# mega_shield_simple.net
KiCad netlist of a schematic drawn in EAGLE
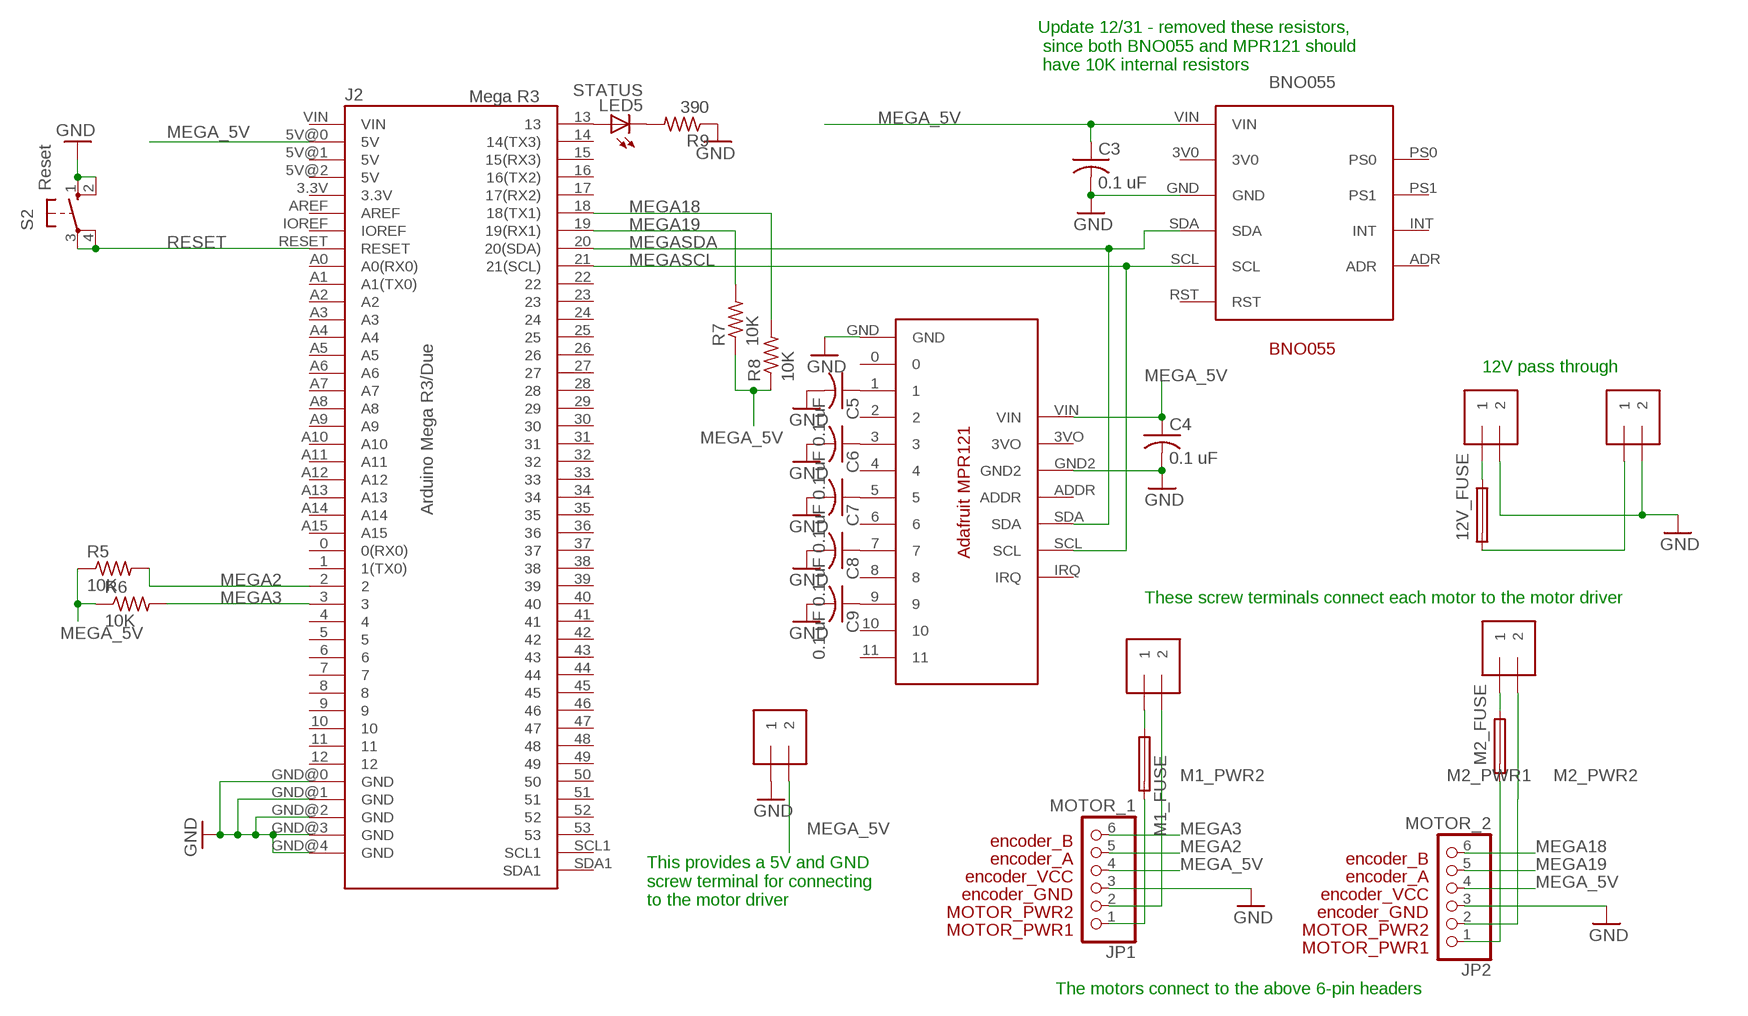
[diagram p0: schematic, sheet 1]

(export (version "E")
  (design (tool "Eeschema 10.0.6"))
  (components
    (comp (ref "5V_OUT")
      (value "1X2-3.5MM")
      (footprint "eagle-import:1X2-3.5MM")
      (libsource (lib "eagle-import") (part "1X2-3.5MM"))
    )
    (comp (ref "12V_FUSE")
      (value "3568")
      (footprint "eagle-import:3568")
      (libsource (lib "eagle-import") (part "3568"))
    )
    (comp (ref "12V_PASS1")
      (value "1X2-3.5MM")
      (footprint "eagle-import:1X2-3.5MM")
      (libsource (lib "eagle-import") (part "1X2-3.5MM"))
    )
    (comp (ref "12V_PASS2")
      (value "1X2-3.5MM")
      (footprint "eagle-import:1X2-3.5MM")
      (libsource (lib "eagle-import") (part "1X2-3.5MM"))
    )
    (comp (ref "BNO055")
      (value "BNO055")
      (footprint "eagle-import:BNO055")
      (libsource (lib "eagle-import") (part "BNO055"))
    )
    (comp (ref "C3")
      (value "0.1 uF")
      (footprint "eagle-import:C025-050X050")
      (libsource (lib "eagle-import") (part "C-US025-050X050"))
    )
    (comp (ref "C4")
      (value "0.1 uF")
      (footprint "eagle-import:C025-050X050")
      (libsource (lib "eagle-import") (part "C-US025-050X050"))
    )
    (comp (ref "C5")
      (value "0.1 uF")
      (footprint "eagle-import:C025-050X050")
      (libsource (lib "eagle-import") (part "C-US025-050X050"))
    )
    (comp (ref "C6")
      (value "0.1 uF")
      (footprint "eagle-import:C025-050X050")
      (libsource (lib "eagle-import") (part "C-US025-050X050"))
    )
    (comp (ref "C7")
      (value "0.1 uF")
      (footprint "eagle-import:C025-050X050")
      (libsource (lib "eagle-import") (part "C-US025-050X050"))
    )
    (comp (ref "C8")
      (value "0.1 uF")
      (footprint "eagle-import:C025-050X050")
      (libsource (lib "eagle-import") (part "C-US025-050X050"))
    )
    (comp (ref "C9")
      (value "0.1 uF")
      (footprint "eagle-import:C025-050X050")
      (libsource (lib "eagle-import") (part "C-US025-050X050"))
    )
    (comp (ref "J2")
      (value "Mega R3")
      (footprint "eagle-import:ARDUINO_MEGA")
      (libsource (lib "eagle-import") (part "ARDUINO-MEGAFULL"))
    )
    (comp (ref "JP1")
      (value "MOTOR_1")
      (footprint "eagle-import:1X06")
      (libsource (lib "eagle-import") (part "PINHD-1X6"))
    )
    (comp (ref "JP2")
      (value "MOTOR_2")
      (footprint "eagle-import:1X06")
      (libsource (lib "eagle-import") (part "PINHD-1X6"))
    )
    (comp (ref "LED5")
      (value "STATUS")
      (footprint "eagle-import:LED3MM")
      (libsource (lib "eagle-import") (part "LED3MM"))
    )
    (comp (ref "M1_FUSE")
      (value "FUSETE5")
      (footprint "eagle-import:TE5")
      (libsource (lib "eagle-import") (part "FUSETE5"))
    )
    (comp (ref "M1_PWR")
      (value "1X2-3.5MM")
      (footprint "eagle-import:1X2-3.5MM")
      (libsource (lib "eagle-import") (part "1X2-3.5MM"))
    )
    (comp (ref "M2_FUSE")
      (value "FUSETE5")
      (footprint "eagle-import:TE5")
      (libsource (lib "eagle-import") (part "FUSETE5"))
    )
    (comp (ref "M2_PWR")
      (value "1X2-3.5MM")
      (footprint "eagle-import:1X2-3.5MM")
      (libsource (lib "eagle-import") (part "1X2-3.5MM"))
    )
    (comp (ref "MPR121")
      (value "ADA_MPR121")
      (footprint "eagle-import:ADA_MPR121")
      (libsource (lib "eagle-import") (part "ADA_MPR121"))
    )
    (comp (ref "R5")
      (value "10K")
      (footprint "eagle-import:0207_10")
      (libsource (lib "eagle-import") (part "R-US_0207/10"))
    )
    (comp (ref "R6")
      (value "10K")
      (footprint "eagle-import:0207_10")
      (libsource (lib "eagle-import") (part "R-US_0207/10"))
    )
    (comp (ref "R7")
      (value "10K")
      (footprint "eagle-import:0207_10")
      (libsource (lib "eagle-import") (part "R-US_0207/10"))
    )
    (comp (ref "R8")
      (value "10K")
      (footprint "eagle-import:0207_10")
      (libsource (lib "eagle-import") (part "R-US_0207/10"))
    )
    (comp (ref "R9")
      (value "390")
      (footprint "eagle-import:0207_10")
      (libsource (lib "eagle-import") (part "R-US_0207/10"))
    )
    (comp (ref "S2")
      (value "Reset")
      (footprint "eagle-import:B3F-10XX")
      (fields (field (name "MPN") "B3F-1000"))
      (libsource (lib "eagle-import") (part "10-XX"))
    )
  )
  (nets
    (net (code "1") (name "/M1_PWR2") (class "Default")
      (node (ref "JP1") (pin "2") (pinfunction "2_2") (pintype "passive"))
      (node (ref "M1_PWR") (pin "2") (pinfunction "2_2") (pintype "passive"))
    )
    (net (code "2") (name "/M2_PWR1") (class "Default")
      (node (ref "JP2") (pin "1") (pinfunction "1_1") (pintype "passive"))
      (node (ref "M2_FUSE") (pin "2") (pinfunction "2_2") (pintype "passive"))
    )
    (net (code "3") (name "/M2_PWR2") (class "Default")
      (node (ref "JP2") (pin "2") (pinfunction "2_2") (pintype "passive"))
      (node (ref "M2_PWR") (pin "2") (pinfunction "2_2") (pintype "passive"))
    )
    (net (code "4") (name "/MEGA2") (class "Default")
      (node (ref "J2") (pin "2") (pinfunction "2_2") (pintype "bidirectional"))
      (node (ref "JP1") (pin "5") (pinfunction "5_5") (pintype "passive"))
      (node (ref "R5") (pin "2") (pinfunction "2_2") (pintype "passive"))
    )
    (net (code "5") (name "/MEGA3") (class "Default")
      (node (ref "J2") (pin "3") (pinfunction "3_3") (pintype "bidirectional"))
      (node (ref "JP1") (pin "6") (pinfunction "6_6") (pintype "passive"))
      (node (ref "R6") (pin "2") (pinfunction "2_2") (pintype "passive"))
    )
    (net (code "6") (name "/MEGA18") (class "Default")
      (node (ref "J2") (pin "18") (pinfunction "18(TX1)_18") (pintype "bidirectional"))
      (node (ref "JP2") (pin "6") (pinfunction "6_6") (pintype "passive"))
      (node (ref "R8") (pin "2") (pinfunction "2_2") (pintype "passive"))
    )
    (net (code "7") (name "/MEGA19") (class "Default")
      (node (ref "J2") (pin "19") (pinfunction "19(RX1)_19") (pintype "bidirectional"))
      (node (ref "JP2") (pin "5") (pinfunction "5_5") (pintype "passive"))
      (node (ref "R7") (pin "2") (pinfunction "2_2") (pintype "passive"))
    )
    (net (code "8") (name "/MEGASCL") (class "Default")
      (node (ref "BNO055") (pin "SCL") (pinfunction "SCL_SCL") (pintype "bidirectional"))
      (node (ref "J2") (pin "21") (pinfunction "21(SCL)_21") (pintype "bidirectional"))
      (node (ref "MPR121") (pin "SCL") (pinfunction "SCL_SCL") (pintype "bidirectional"))
    )
    (net (code "9") (name "/MEGASDA") (class "Default")
      (node (ref "BNO055") (pin "SDA") (pinfunction "SDA_SDA") (pintype "bidirectional"))
      (node (ref "J2") (pin "20") (pinfunction "20(SDA)_20") (pintype "bidirectional"))
      (node (ref "MPR121") (pin "SDA") (pinfunction "SDA_SDA") (pintype "bidirectional"))
    )
    (net (code "10") (name "/MEGA_5V") (class "Default")
      (node (ref "5V_OUT") (pin "2") (pinfunction "2_2") (pintype "passive"))
      (node (ref "BNO055") (pin "VIN") (pinfunction "VIN_VIN") (pintype "bidirectional"))
      (node (ref "C3") (pin "1") (pinfunction "1_1") (pintype "passive"))
      (node (ref "C4") (pin "1") (pinfunction "1_1") (pintype "passive"))
      (node (ref "J2") (pin "5V@0") (pinfunction "5V_5V@0") (pintype "bidirectional"))
      (node (ref "JP1") (pin "4") (pinfunction "4_4") (pintype "passive"))
      (node (ref "JP2") (pin "4") (pinfunction "4_4") (pintype "passive"))
      (node (ref "MPR121") (pin "VIN") (pinfunction "VIN_VIN") (pintype "bidirectional"))
      (node (ref "R5") (pin "1") (pinfunction "1_1") (pintype "passive"))
      (node (ref "R6") (pin "1") (pinfunction "1_1") (pintype "passive"))
      (node (ref "R7") (pin "1") (pinfunction "1_1") (pintype "passive"))
      (node (ref "R8") (pin "1") (pinfunction "1_1") (pintype "passive"))
    )
    (net (code "11") (name "/RESET") (class "Default")
      (node (ref "J2") (pin "RESET") (pinfunction "RESET_RESET") (pintype "bidirectional"))
      (node (ref "S2") (pin "3") (pinfunction "P_3") (pintype "passive"))
      (node (ref "S2") (pin "4") (pinfunction "P1_4") (pintype "passive"))
    )
    (net (code "12") (name "GND") (class "Default")
      (node (ref "12V_PASS1") (pin "2") (pinfunction "2_2") (pintype "passive"))
      (node (ref "12V_PASS2") (pin "2") (pinfunction "2_2") (pintype "passive"))
      (node (ref "5V_OUT") (pin "1") (pinfunction "1_1") (pintype "passive"))
      (node (ref "BNO055") (pin "GND") (pinfunction "GND_GND") (pintype "bidirectional"))
      (node (ref "C3") (pin "2") (pinfunction "2_2") (pintype "passive"))
      (node (ref "C4") (pin "2") (pinfunction "2_2") (pintype "passive"))
      (node (ref "C5") (pin "2") (pinfunction "2_2") (pintype "passive"))
      (node (ref "C6") (pin "2") (pinfunction "2_2") (pintype "passive"))
      (node (ref "C7") (pin "2") (pinfunction "2_2") (pintype "passive"))
      (node (ref "C8") (pin "2") (pinfunction "2_2") (pintype "passive"))
      (node (ref "C9") (pin "2") (pinfunction "2_2") (pintype "passive"))
      (node (ref "J2") (pin "GND@0") (pinfunction "GND_GND@0") (pintype "bidirectional"))
      (node (ref "J2") (pin "GND@1") (pinfunction "GND_GND@1") (pintype "bidirectional"))
      (node (ref "J2") (pin "GND@2") (pinfunction "GND_GND@2") (pintype "bidirectional"))
      (node (ref "J2") (pin "GND@3") (pinfunction "GND_GND@3") (pintype "bidirectional"))
      (node (ref "J2") (pin "GND@4") (pinfunction "GND_GND@4") (pintype "bidirectional"))
      (node (ref "JP1") (pin "3") (pinfunction "3_3") (pintype "passive"))
      (node (ref "JP2") (pin "3") (pinfunction "3_3") (pintype "passive"))
      (node (ref "MPR121") (pin "GND") (pinfunction "GND_GND") (pintype "bidirectional"))
      (node (ref "MPR121") (pin "GND2") (pinfunction "GND2_GND2") (pintype "bidirectional"))
      (node (ref "R9") (pin "1") (pinfunction "1_1") (pintype "passive"))
      (node (ref "S2") (pin "1") (pinfunction "S_1") (pintype "passive"))
      (node (ref "S2") (pin "2") (pinfunction "S1_2") (pintype "passive"))
    )
    (net (code "13") (name "Net-(12V_FUSE-1-Pad2)") (class "Default")
      (node (ref "12V_FUSE") (pin "1") (pinfunction "1_1") (pintype "passive"))
      (node (ref "12V_FUSE") (pin "2") (pinfunction "1_2") (pintype "passive"))
      (node (ref "12V_PASS2") (pin "1") (pinfunction "1_1") (pintype "passive"))
    )
    (net (code "14") (name "Net-(12V_FUSE-2-Pad3)") (class "Default")
      (node (ref "12V_FUSE") (pin "3") (pinfunction "2_3") (pintype "passive"))
      (node (ref "12V_FUSE") (pin "4") (pinfunction "2_4") (pintype "passive"))
      (node (ref "12V_PASS1") (pin "1") (pinfunction "1_1") (pintype "passive"))
    )
    (net (code "15") (name "Net-(C5-Pad1)") (class "Default")
      (node (ref "C5") (pin "1") (pinfunction "1_1") (pintype "passive"))
      (node (ref "MPR121") (pin "1") (pinfunction "1_1") (pintype "bidirectional"))
    )
    (net (code "16") (name "Net-(C6-Pad1)") (class "Default")
      (node (ref "C6") (pin "1") (pinfunction "1_1") (pintype "passive"))
      (node (ref "MPR121") (pin "3") (pinfunction "3_3") (pintype "bidirectional"))
    )
    (net (code "17") (name "Net-(C7-Pad1)") (class "Default")
      (node (ref "C7") (pin "1") (pinfunction "1_1") (pintype "passive"))
      (node (ref "MPR121") (pin "5") (pinfunction "5_5") (pintype "bidirectional"))
    )
    (net (code "18") (name "Net-(C8-Pad1)") (class "Default")
      (node (ref "C8") (pin "1") (pinfunction "1_1") (pintype "passive"))
      (node (ref "MPR121") (pin "7") (pinfunction "7_7") (pintype "bidirectional"))
    )
    (net (code "19") (name "Net-(C9-Pad1)") (class "Default")
      (node (ref "C9") (pin "1") (pinfunction "1_1") (pintype "passive"))
      (node (ref "MPR121") (pin "9") (pinfunction "9_9") (pintype "bidirectional"))
    )
    (net (code "20") (name "Net-(J2-Pad13)") (class "Default")
      (node (ref "J2") (pin "13") (pinfunction "13_13") (pintype "bidirectional"))
      (node (ref "LED5") (pin "A") (pinfunction "A_A") (pintype "passive"))
    )
    (net (code "21") (name "Net-(JP1-Pad1)") (class "Default")
      (node (ref "JP1") (pin "1") (pinfunction "1_1") (pintype "passive"))
      (node (ref "M1_FUSE") (pin "2") (pinfunction "2_2") (pintype "passive"))
    )
    (net (code "22") (name "Net-(LED5-C)") (class "Default")
      (node (ref "LED5") (pin "K") (pinfunction "C_K") (pintype "passive"))
      (node (ref "R9") (pin "2") (pinfunction "2_2") (pintype "passive"))
    )
    (net (code "23") (name "Net-(M1_FUSE-Pad1)") (class "Default")
      (node (ref "M1_FUSE") (pin "1") (pinfunction "1_1") (pintype "passive"))
      (node (ref "M1_PWR") (pin "1") (pinfunction "1_1") (pintype "passive"))
    )
    (net (code "24") (name "Net-(M2_FUSE-Pad1)") (class "Default")
      (node (ref "M2_FUSE") (pin "1") (pinfunction "1_1") (pintype "passive"))
      (node (ref "M2_PWR") (pin "1") (pinfunction "1_1") (pintype "passive"))
    )
    (net (code "25") (name "unconnected-(BNO055-Pad3V0)") (class "Default")
      (node (ref "BNO055") (pin "3V0") (pinfunction "3V0_3V0") (pintype "bidirectional"))
    )
    (net (code "26") (name "unconnected-(BNO055-PadADR)") (class "Default")
      (node (ref "BNO055") (pin "ADR") (pinfunction "ADR_ADR") (pintype "bidirectional"))
    )
    (net (code "27") (name "unconnected-(BNO055-PadINT)") (class "Default")
      (node (ref "BNO055") (pin "INT") (pinfunction "INT_INT") (pintype "bidirectional"))
    )
    (net (code "28") (name "unconnected-(BNO055-PadPS0)") (class "Default")
      (node (ref "BNO055") (pin "PS0") (pinfunction "PS0_PS0") (pintype "bidirectional"))
    )
    (net (code "29") (name "unconnected-(BNO055-PadPS1)") (class "Default")
      (node (ref "BNO055") (pin "PS1") (pinfunction "PS1_PS1") (pintype "bidirectional"))
    )
    (net (code "30") (name "unconnected-(BNO055-PadRST)") (class "Default")
      (node (ref "BNO055") (pin "RST") (pinfunction "RST_RST") (pintype "bidirectional"))
    )
    (net (code "31") (name "unconnected-(J2-0(RX0)-Pad0)") (class "Default")
      (node (ref "J2") (pin "0") (pinfunction "0(RX0)_0") (pintype "bidirectional"))
    )
    (net (code "32") (name "unconnected-(J2-1(TX0)-Pad1)") (class "Default")
      (node (ref "J2") (pin "1") (pinfunction "1(TX0)_1") (pintype "bidirectional"))
    )
    (net (code "33") (name "unconnected-(J2-5V-Pad5V@1)") (class "Default")
      (node (ref "J2") (pin "5V@1") (pinfunction "5V_5V@1") (pintype "bidirectional"))
    )
    (net (code "34") (name "unconnected-(J2-5V-Pad5V@2)") (class "Default")
      (node (ref "J2") (pin "5V@2") (pinfunction "5V_5V@2") (pintype "bidirectional"))
    )
    (net (code "35") (name "unconnected-(J2-14(TX3)-Pad14)") (class "Default")
      (node (ref "J2") (pin "14") (pinfunction "14(TX3)_14") (pintype "bidirectional"))
    )
    (net (code "36") (name "unconnected-(J2-15(RX3)-Pad15)") (class "Default")
      (node (ref "J2") (pin "15") (pinfunction "15(RX3)_15") (pintype "bidirectional"))
    )
    (net (code "37") (name "unconnected-(J2-16(TX2)-Pad16)") (class "Default")
      (node (ref "J2") (pin "16") (pinfunction "16(TX2)_16") (pintype "bidirectional"))
    )
    (net (code "38") (name "unconnected-(J2-17(RX2)-Pad17)") (class "Default")
      (node (ref "J2") (pin "17") (pinfunction "17(RX2)_17") (pintype "bidirectional"))
    )
    (net (code "39") (name "unconnected-(J2-A0(RX0)-PadA0)") (class "Default")
      (node (ref "J2") (pin "A0") (pinfunction "A0(RX0)_A0") (pintype "bidirectional"))
    )
    (net (code "40") (name "unconnected-(J2-A1(TX0)-PadA1)") (class "Default")
      (node (ref "J2") (pin "A1") (pinfunction "A1(TX0)_A1") (pintype "bidirectional"))
    )
    (net (code "41") (name "unconnected-(J2-Pad3.3V)") (class "Default")
      (node (ref "J2") (pin "3.3V") (pinfunction "3.3V_3.3V") (pintype "bidirectional"))
    )
    (net (code "42") (name "unconnected-(J2-Pad4)") (class "Default")
      (node (ref "J2") (pin "4") (pinfunction "4_4") (pintype "bidirectional"))
    )
    (net (code "43") (name "unconnected-(J2-Pad5)") (class "Default")
      (node (ref "J2") (pin "5") (pinfunction "5_5") (pintype "bidirectional"))
    )
    (net (code "44") (name "unconnected-(J2-Pad6)") (class "Default")
      (node (ref "J2") (pin "6") (pinfunction "6_6") (pintype "bidirectional"))
    )
    (net (code "45") (name "unconnected-(J2-Pad7)") (class "Default")
      (node (ref "J2") (pin "7") (pinfunction "7_7") (pintype "bidirectional"))
    )
    (net (code "46") (name "unconnected-(J2-Pad8)") (class "Default")
      (node (ref "J2") (pin "8") (pinfunction "8_8") (pintype "bidirectional"))
    )
    (net (code "47") (name "unconnected-(J2-Pad9)") (class "Default")
      (node (ref "J2") (pin "9") (pinfunction "9_9") (pintype "bidirectional"))
    )
    (net (code "48") (name "unconnected-(J2-Pad10)") (class "Default")
      (node (ref "J2") (pin "10") (pinfunction "10_10") (pintype "bidirectional"))
    )
    (net (code "49") (name "unconnected-(J2-Pad11)") (class "Default")
      (node (ref "J2") (pin "11") (pinfunction "11_11") (pintype "bidirectional"))
    )
    (net (code "50") (name "unconnected-(J2-Pad12)") (class "Default")
      (node (ref "J2") (pin "12") (pinfunction "12_12") (pintype "bidirectional"))
    )
    (net (code "51") (name "unconnected-(J2-Pad22)") (class "Default")
      (node (ref "J2") (pin "22") (pinfunction "22_22") (pintype "bidirectional"))
    )
    (net (code "52") (name "unconnected-(J2-Pad23)") (class "Default")
      (node (ref "J2") (pin "23") (pinfunction "23_23") (pintype "bidirectional"))
    )
    (net (code "53") (name "unconnected-(J2-Pad24)") (class "Default")
      (node (ref "J2") (pin "24") (pinfunction "24_24") (pintype "bidirectional"))
    )
    (net (code "54") (name "unconnected-(J2-Pad25)") (class "Default")
      (node (ref "J2") (pin "25") (pinfunction "25_25") (pintype "bidirectional"))
    )
    (net (code "55") (name "unconnected-(J2-Pad26)") (class "Default")
      (node (ref "J2") (pin "26") (pinfunction "26_26") (pintype "bidirectional"))
    )
    (net (code "56") (name "unconnected-(J2-Pad27)") (class "Default")
      (node (ref "J2") (pin "27") (pinfunction "27_27") (pintype "bidirectional"))
    )
    (net (code "57") (name "unconnected-(J2-Pad28)") (class "Default")
      (node (ref "J2") (pin "28") (pinfunction "28_28") (pintype "bidirectional"))
    )
    (net (code "58") (name "unconnected-(J2-Pad29)") (class "Default")
      (node (ref "J2") (pin "29") (pinfunction "29_29") (pintype "bidirectional"))
    )
    (net (code "59") (name "unconnected-(J2-Pad30)") (class "Default")
      (node (ref "J2") (pin "30") (pinfunction "30_30") (pintype "bidirectional"))
    )
    (net (code "60") (name "unconnected-(J2-Pad31)") (class "Default")
      (node (ref "J2") (pin "31") (pinfunction "31_31") (pintype "bidirectional"))
    )
    (net (code "61") (name "unconnected-(J2-Pad32)") (class "Default")
      (node (ref "J2") (pin "32") (pinfunction "32_32") (pintype "bidirectional"))
    )
    (net (code "62") (name "unconnected-(J2-Pad33)") (class "Default")
      (node (ref "J2") (pin "33") (pinfunction "33_33") (pintype "bidirectional"))
    )
    (net (code "63") (name "unconnected-(J2-Pad34)") (class "Default")
      (node (ref "J2") (pin "34") (pinfunction "34_34") (pintype "bidirectional"))
    )
    (net (code "64") (name "unconnected-(J2-Pad35)") (class "Default")
      (node (ref "J2") (pin "35") (pinfunction "35_35") (pintype "bidirectional"))
    )
    (net (code "65") (name "unconnected-(J2-Pad36)") (class "Default")
      (node (ref "J2") (pin "36") (pinfunction "36_36") (pintype "bidirectional"))
    )
    (net (code "66") (name "unconnected-(J2-Pad37)") (class "Default")
      (node (ref "J2") (pin "37") (pinfunction "37_37") (pintype "bidirectional"))
    )
    (net (code "67") (name "unconnected-(J2-Pad38)") (class "Default")
      (node (ref "J2") (pin "38") (pinfunction "38_38") (pintype "bidirectional"))
    )
    (net (code "68") (name "unconnected-(J2-Pad39)") (class "Default")
      (node (ref "J2") (pin "39") (pinfunction "39_39") (pintype "bidirectional"))
    )
    (net (code "69") (name "unconnected-(J2-Pad40)") (class "Default")
      (node (ref "J2") (pin "40") (pinfunction "40_40") (pintype "bidirectional"))
    )
    (net (code "70") (name "unconnected-(J2-Pad41)") (class "Default")
      (node (ref "J2") (pin "41") (pinfunction "41_41") (pintype "bidirectional"))
    )
    (net (code "71") (name "unconnected-(J2-Pad42)") (class "Default")
      (node (ref "J2") (pin "42") (pinfunction "42_42") (pintype "bidirectional"))
    )
    (net (code "72") (name "unconnected-(J2-Pad43)") (class "Default")
      (node (ref "J2") (pin "43") (pinfunction "43_43") (pintype "bidirectional"))
    )
    (net (code "73") (name "unconnected-(J2-Pad44)") (class "Default")
      (node (ref "J2") (pin "44") (pinfunction "44_44") (pintype "bidirectional"))
    )
    (net (code "74") (name "unconnected-(J2-Pad45)") (class "Default")
      (node (ref "J2") (pin "45") (pinfunction "45_45") (pintype "bidirectional"))
    )
    (net (code "75") (name "unconnected-(J2-Pad46)") (class "Default")
      (node (ref "J2") (pin "46") (pinfunction "46_46") (pintype "bidirectional"))
    )
    (net (code "76") (name "unconnected-(J2-Pad47)") (class "Default")
      (node (ref "J2") (pin "47") (pinfunction "47_47") (pintype "bidirectional"))
    )
    (net (code "77") (name "unconnected-(J2-Pad48)") (class "Default")
      (node (ref "J2") (pin "48") (pinfunction "48_48") (pintype "bidirectional"))
    )
    (net (code "78") (name "unconnected-(J2-Pad49)") (class "Default")
      (node (ref "J2") (pin "49") (pinfunction "49_49") (pintype "bidirectional"))
    )
    (net (code "79") (name "unconnected-(J2-Pad50)") (class "Default")
      (node (ref "J2") (pin "50") (pinfunction "50_50") (pintype "bidirectional"))
    )
    (net (code "80") (name "unconnected-(J2-Pad51)") (class "Default")
      (node (ref "J2") (pin "51") (pinfunction "51_51") (pintype "bidirectional"))
    )
    (net (code "81") (name "unconnected-(J2-Pad52)") (class "Default")
      (node (ref "J2") (pin "52") (pinfunction "52_52") (pintype "bidirectional"))
    )
    (net (code "82") (name "unconnected-(J2-Pad53)") (class "Default")
      (node (ref "J2") (pin "53") (pinfunction "53_53") (pintype "bidirectional"))
    )
    (net (code "83") (name "unconnected-(J2-PadA2)") (class "Default")
      (node (ref "J2") (pin "A2") (pinfunction "A2_A2") (pintype "bidirectional"))
    )
    (net (code "84") (name "unconnected-(J2-PadA3)") (class "Default")
      (node (ref "J2") (pin "A3") (pinfunction "A3_A3") (pintype "bidirectional"))
    )
    (net (code "85") (name "unconnected-(J2-PadA4)") (class "Default")
      (node (ref "J2") (pin "A4") (pinfunction "A4_A4") (pintype "bidirectional"))
    )
    (net (code "86") (name "unconnected-(J2-PadA5)") (class "Default")
      (node (ref "J2") (pin "A5") (pinfunction "A5_A5") (pintype "bidirectional"))
    )
    (net (code "87") (name "unconnected-(J2-PadA6)") (class "Default")
      (node (ref "J2") (pin "A6") (pinfunction "A6_A6") (pintype "bidirectional"))
    )
    (net (code "88") (name "unconnected-(J2-PadA7)") (class "Default")
      (node (ref "J2") (pin "A7") (pinfunction "A7_A7") (pintype "bidirectional"))
    )
    (net (code "89") (name "unconnected-(J2-PadA8)") (class "Default")
      (node (ref "J2") (pin "A8") (pinfunction "A8_A8") (pintype "bidirectional"))
    )
    (net (code "90") (name "unconnected-(J2-PadA9)") (class "Default")
      (node (ref "J2") (pin "A9") (pinfunction "A9_A9") (pintype "bidirectional"))
    )
    (net (code "91") (name "unconnected-(J2-PadA10)") (class "Default")
      (node (ref "J2") (pin "A10") (pinfunction "A10_A10") (pintype "bidirectional"))
    )
    (net (code "92") (name "unconnected-(J2-PadA11)") (class "Default")
      (node (ref "J2") (pin "A11") (pinfunction "A11_A11") (pintype "bidirectional"))
    )
    (net (code "93") (name "unconnected-(J2-PadA12)") (class "Default")
      (node (ref "J2") (pin "A12") (pinfunction "A12_A12") (pintype "bidirectional"))
    )
    (net (code "94") (name "unconnected-(J2-PadA13)") (class "Default")
      (node (ref "J2") (pin "A13") (pinfunction "A13_A13") (pintype "bidirectional"))
    )
    (net (code "95") (name "unconnected-(J2-PadA14)") (class "Default")
      (node (ref "J2") (pin "A14") (pinfunction "A14_A14") (pintype "bidirectional"))
    )
    (net (code "96") (name "unconnected-(J2-PadA15)") (class "Default")
      (node (ref "J2") (pin "A15") (pinfunction "A15_A15") (pintype "bidirectional"))
    )
    (net (code "97") (name "unconnected-(J2-PadAREF)") (class "Default")
      (node (ref "J2") (pin "AREF") (pinfunction "AREF_AREF") (pintype "bidirectional"))
    )
    (net (code "98") (name "unconnected-(J2-PadIOREF)") (class "Default")
      (node (ref "J2") (pin "IOREF") (pinfunction "IOREF_IOREF") (pintype "bidirectional"))
    )
    (net (code "99") (name "unconnected-(J2-PadSCL1)") (class "Default")
      (node (ref "J2") (pin "SCL1") (pinfunction "SCL1_SCL1") (pintype "bidirectional"))
    )
    (net (code "100") (name "unconnected-(J2-PadSDA1)") (class "Default")
      (node (ref "J2") (pin "SDA1") (pinfunction "SDA1_SDA1") (pintype "bidirectional"))
    )
    (net (code "101") (name "unconnected-(J2-PadVIN)") (class "Default")
      (node (ref "J2") (pin "VIN") (pinfunction "VIN_VIN") (pintype "bidirectional"))
    )
    (net (code "102") (name "unconnected-(MPR121-Pad0)") (class "Default")
      (node (ref "MPR121") (pin "0") (pinfunction "0_0") (pintype "bidirectional"))
    )
    (net (code "103") (name "unconnected-(MPR121-Pad2)") (class "Default")
      (node (ref "MPR121") (pin "2") (pinfunction "2_2") (pintype "bidirectional"))
    )
    (net (code "104") (name "unconnected-(MPR121-Pad3VO)") (class "Default")
      (node (ref "MPR121") (pin "3VO") (pinfunction "3VO_3VO") (pintype "bidirectional"))
    )
    (net (code "105") (name "unconnected-(MPR121-Pad4)") (class "Default")
      (node (ref "MPR121") (pin "4") (pinfunction "4_4") (pintype "bidirectional"))
    )
    (net (code "106") (name "unconnected-(MPR121-Pad6)") (class "Default")
      (node (ref "MPR121") (pin "6") (pinfunction "6_6") (pintype "bidirectional"))
    )
    (net (code "107") (name "unconnected-(MPR121-Pad8)") (class "Default")
      (node (ref "MPR121") (pin "8") (pinfunction "8_8") (pintype "bidirectional"))
    )
    (net (code "108") (name "unconnected-(MPR121-Pad10)") (class "Default")
      (node (ref "MPR121") (pin "10") (pinfunction "10_10") (pintype "bidirectional"))
    )
    (net (code "109") (name "unconnected-(MPR121-Pad11)") (class "Default")
      (node (ref "MPR121") (pin "11") (pinfunction "11_11") (pintype "bidirectional"))
    )
    (net (code "110") (name "unconnected-(MPR121-PadADDR)") (class "Default")
      (node (ref "MPR121") (pin "ADDR") (pinfunction "ADDR_ADDR") (pintype "bidirectional"))
    )
    (net (code "111") (name "unconnected-(MPR121-PadIRQ)") (class "Default")
      (node (ref "MPR121") (pin "IRQ") (pinfunction "IRQ_IRQ") (pintype "bidirectional"))
    )
  )
)
